# CharlieplexNameTag.net
KiCad netlist of a schematic drawn in EAGLE
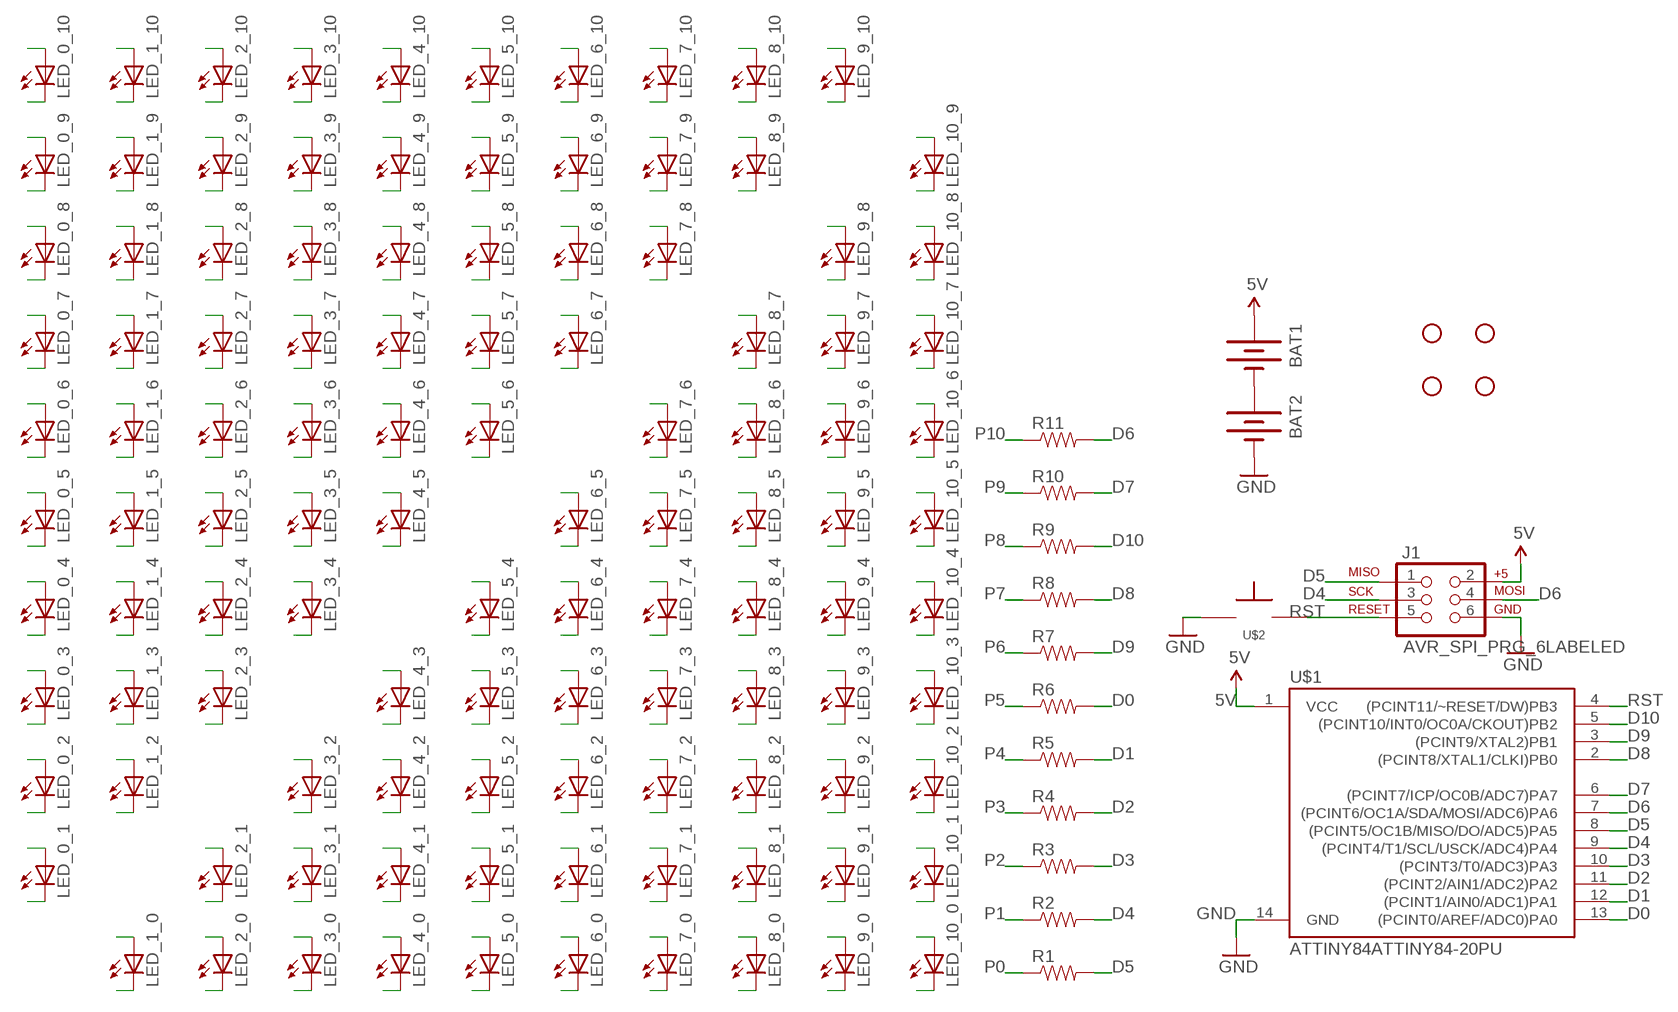
[diagram p0: schematic, sheet 1]

(export (version "E")
  (design (tool "Eeschema 10.0.6"))
  (components
    (comp (ref "BAT1")
      (value "BATTERYAAA")
      (footprint "eagle-import:BATTERY-AAA")
      (libsource (lib "eagle-import") (part "BATTERYAAA"))
    )
    (comp (ref "BAT2")
      (value "BATTERYAAA")
      (footprint "eagle-import:BATTERY-AAA")
      (libsource (lib "eagle-import") (part "BATTERYAAA"))
    )
    (comp (ref "J1")
      (value "AVR_SPI_PRG_6LABELED")
      (footprint "eagle-import:2X3-NS")
      (libsource (lib "eagle-import") (part "AVR_SPI_PRG_6LABELED"))
    )
    (comp (ref "LED_0_1")
      (value "LED3MM")
      (footprint "eagle-import:LED3MM")
      (libsource (lib "eagle-import") (part "LED3MM"))
    )
    (comp (ref "LED_0_2")
      (value "LED3MM")
      (footprint "eagle-import:LED3MM")
      (libsource (lib "eagle-import") (part "LED3MM"))
    )
    (comp (ref "LED_0_3")
      (value "LED3MM")
      (footprint "eagle-import:LED3MM")
      (libsource (lib "eagle-import") (part "LED3MM"))
    )
    (comp (ref "LED_0_4")
      (value "LED3MM")
      (footprint "eagle-import:LED3MM")
      (libsource (lib "eagle-import") (part "LED3MM"))
    )
    (comp (ref "LED_0_5")
      (value "LED3MM")
      (footprint "eagle-import:LED3MM")
      (libsource (lib "eagle-import") (part "LED3MM"))
    )
    (comp (ref "LED_0_6")
      (value "LED3MM")
      (footprint "eagle-import:LED3MM")
      (libsource (lib "eagle-import") (part "LED3MM"))
    )
    (comp (ref "LED_0_7")
      (value "LED3MM")
      (footprint "eagle-import:LED3MM")
      (libsource (lib "eagle-import") (part "LED3MM"))
    )
    (comp (ref "LED_0_8")
      (value "LED3MM")
      (footprint "eagle-import:LED3MM")
      (libsource (lib "eagle-import") (part "LED3MM"))
    )
    (comp (ref "LED_0_9")
      (value "LED3MM")
      (footprint "eagle-import:LED3MM")
      (libsource (lib "eagle-import") (part "LED3MM"))
    )
    (comp (ref "LED_0_10")
      (value "LED3MM")
      (footprint "eagle-import:LED3MM")
      (libsource (lib "eagle-import") (part "LED3MM"))
    )
    (comp (ref "LED_1_0")
      (value "LED3MM")
      (footprint "eagle-import:LED3MM")
      (libsource (lib "eagle-import") (part "LED3MM"))
    )
    (comp (ref "LED_1_2")
      (value "LED3MM")
      (footprint "eagle-import:LED3MM")
      (libsource (lib "eagle-import") (part "LED3MM"))
    )
    (comp (ref "LED_1_3")
      (value "LED3MM")
      (footprint "eagle-import:LED3MM")
      (libsource (lib "eagle-import") (part "LED3MM"))
    )
    (comp (ref "LED_1_4")
      (value "LED3MM")
      (footprint "eagle-import:LED3MM")
      (libsource (lib "eagle-import") (part "LED3MM"))
    )
    (comp (ref "LED_1_5")
      (value "LED3MM")
      (footprint "eagle-import:LED3MM")
      (libsource (lib "eagle-import") (part "LED3MM"))
    )
    (comp (ref "LED_1_6")
      (value "LED3MM")
      (footprint "eagle-import:LED3MM")
      (libsource (lib "eagle-import") (part "LED3MM"))
    )
    (comp (ref "LED_1_7")
      (value "LED3MM")
      (footprint "eagle-import:LED3MM")
      (libsource (lib "eagle-import") (part "LED3MM"))
    )
    (comp (ref "LED_1_8")
      (value "LED3MM")
      (footprint "eagle-import:LED3MM")
      (libsource (lib "eagle-import") (part "LED3MM"))
    )
    (comp (ref "LED_1_9")
      (value "LED3MM")
      (footprint "eagle-import:LED3MM")
      (libsource (lib "eagle-import") (part "LED3MM"))
    )
    (comp (ref "LED_1_10")
      (value "LED3MM")
      (footprint "eagle-import:LED3MM")
      (libsource (lib "eagle-import") (part "LED3MM"))
    )
    (comp (ref "LED_2_0")
      (value "LED3MM")
      (footprint "eagle-import:LED3MM")
      (libsource (lib "eagle-import") (part "LED3MM"))
    )
    (comp (ref "LED_2_1")
      (value "LED3MM")
      (footprint "eagle-import:LED3MM")
      (libsource (lib "eagle-import") (part "LED3MM"))
    )
    (comp (ref "LED_2_3")
      (value "LED3MM")
      (footprint "eagle-import:LED3MM")
      (libsource (lib "eagle-import") (part "LED3MM"))
    )
    (comp (ref "LED_2_4")
      (value "LED3MM")
      (footprint "eagle-import:LED3MM")
      (libsource (lib "eagle-import") (part "LED3MM"))
    )
    (comp (ref "LED_2_5")
      (value "LED3MM")
      (footprint "eagle-import:LED3MM")
      (libsource (lib "eagle-import") (part "LED3MM"))
    )
    (comp (ref "LED_2_6")
      (value "LED3MM")
      (footprint "eagle-import:LED3MM")
      (libsource (lib "eagle-import") (part "LED3MM"))
    )
    (comp (ref "LED_2_7")
      (value "LED3MM")
      (footprint "eagle-import:LED3MM")
      (libsource (lib "eagle-import") (part "LED3MM"))
    )
    (comp (ref "LED_2_8")
      (value "LED3MM")
      (footprint "eagle-import:LED3MM")
      (libsource (lib "eagle-import") (part "LED3MM"))
    )
    (comp (ref "LED_2_9")
      (value "LED3MM")
      (footprint "eagle-import:LED3MM")
      (libsource (lib "eagle-import") (part "LED3MM"))
    )
    (comp (ref "LED_2_10")
      (value "LED3MM")
      (footprint "eagle-import:LED3MM")
      (libsource (lib "eagle-import") (part "LED3MM"))
    )
    (comp (ref "LED_3_0")
      (value "LED3MM")
      (footprint "eagle-import:LED3MM")
      (libsource (lib "eagle-import") (part "LED3MM"))
    )
    (comp (ref "LED_3_1")
      (value "LED3MM")
      (footprint "eagle-import:LED3MM")
      (libsource (lib "eagle-import") (part "LED3MM"))
    )
    (comp (ref "LED_3_2")
      (value "LED3MM")
      (footprint "eagle-import:LED3MM")
      (libsource (lib "eagle-import") (part "LED3MM"))
    )
    (comp (ref "LED_3_4")
      (value "LED3MM")
      (footprint "eagle-import:LED3MM")
      (libsource (lib "eagle-import") (part "LED3MM"))
    )
    (comp (ref "LED_3_5")
      (value "LED3MM")
      (footprint "eagle-import:LED3MM")
      (libsource (lib "eagle-import") (part "LED3MM"))
    )
    (comp (ref "LED_3_6")
      (value "LED3MM")
      (footprint "eagle-import:LED3MM")
      (libsource (lib "eagle-import") (part "LED3MM"))
    )
    (comp (ref "LED_3_7")
      (value "LED3MM")
      (footprint "eagle-import:LED3MM")
      (libsource (lib "eagle-import") (part "LED3MM"))
    )
    (comp (ref "LED_3_8")
      (value "LED3MM")
      (footprint "eagle-import:LED3MM")
      (libsource (lib "eagle-import") (part "LED3MM"))
    )
    (comp (ref "LED_3_9")
      (value "LED3MM")
      (footprint "eagle-import:LED3MM")
      (libsource (lib "eagle-import") (part "LED3MM"))
    )
    (comp (ref "LED_3_10")
      (value "LED3MM")
      (footprint "eagle-import:LED3MM")
      (libsource (lib "eagle-import") (part "LED3MM"))
    )
    (comp (ref "LED_4_0")
      (value "LED3MM")
      (footprint "eagle-import:LED3MM")
      (libsource (lib "eagle-import") (part "LED3MM"))
    )
    (comp (ref "LED_4_1")
      (value "LED3MM")
      (footprint "eagle-import:LED3MM")
      (libsource (lib "eagle-import") (part "LED3MM"))
    )
    (comp (ref "LED_4_2")
      (value "LED3MM")
      (footprint "eagle-import:LED3MM")
      (libsource (lib "eagle-import") (part "LED3MM"))
    )
    (comp (ref "LED_4_3")
      (value "LED3MM")
      (footprint "eagle-import:LED3MM")
      (libsource (lib "eagle-import") (part "LED3MM"))
    )
    (comp (ref "LED_4_5")
      (value "LED3MM")
      (footprint "eagle-import:LED3MM")
      (libsource (lib "eagle-import") (part "LED3MM"))
    )
    (comp (ref "LED_4_6")
      (value "LED3MM")
      (footprint "eagle-import:LED3MM")
      (libsource (lib "eagle-import") (part "LED3MM"))
    )
    (comp (ref "LED_4_7")
      (value "LED3MM")
      (footprint "eagle-import:LED3MM")
      (libsource (lib "eagle-import") (part "LED3MM"))
    )
    (comp (ref "LED_4_8")
      (value "LED3MM")
      (footprint "eagle-import:LED3MM")
      (libsource (lib "eagle-import") (part "LED3MM"))
    )
    (comp (ref "LED_4_9")
      (value "LED3MM")
      (footprint "eagle-import:LED3MM")
      (libsource (lib "eagle-import") (part "LED3MM"))
    )
    (comp (ref "LED_4_10")
      (value "LED3MM")
      (footprint "eagle-import:LED3MM")
      (libsource (lib "eagle-import") (part "LED3MM"))
    )
    (comp (ref "LED_5_0")
      (value "LED3MM")
      (footprint "eagle-import:LED3MM")
      (libsource (lib "eagle-import") (part "LED3MM"))
    )
    (comp (ref "LED_5_1")
      (value "LED3MM")
      (footprint "eagle-import:LED3MM")
      (libsource (lib "eagle-import") (part "LED3MM"))
    )
    (comp (ref "LED_5_2")
      (value "LED3MM")
      (footprint "eagle-import:LED3MM")
      (libsource (lib "eagle-import") (part "LED3MM"))
    )
    (comp (ref "LED_5_3")
      (value "LED3MM")
      (footprint "eagle-import:LED3MM")
      (libsource (lib "eagle-import") (part "LED3MM"))
    )
    (comp (ref "LED_5_4")
      (value "LED3MM")
      (footprint "eagle-import:LED3MM")
      (libsource (lib "eagle-import") (part "LED3MM"))
    )
    (comp (ref "LED_5_6")
      (value "LED3MM")
      (footprint "eagle-import:LED3MM")
      (libsource (lib "eagle-import") (part "LED3MM"))
    )
    (comp (ref "LED_5_7")
      (value "LED3MM")
      (footprint "eagle-import:LED3MM")
      (libsource (lib "eagle-import") (part "LED3MM"))
    )
    (comp (ref "LED_5_8")
      (value "LED3MM")
      (footprint "eagle-import:LED3MM")
      (libsource (lib "eagle-import") (part "LED3MM"))
    )
    (comp (ref "LED_5_9")
      (value "LED3MM")
      (footprint "eagle-import:LED3MM")
      (libsource (lib "eagle-import") (part "LED3MM"))
    )
    (comp (ref "LED_5_10")
      (value "LED3MM")
      (footprint "eagle-import:LED3MM")
      (libsource (lib "eagle-import") (part "LED3MM"))
    )
    (comp (ref "LED_6_0")
      (value "LED3MM")
      (footprint "eagle-import:LED3MM")
      (libsource (lib "eagle-import") (part "LED3MM"))
    )
    (comp (ref "LED_6_1")
      (value "LED3MM")
      (footprint "eagle-import:LED3MM")
      (libsource (lib "eagle-import") (part "LED3MM"))
    )
    (comp (ref "LED_6_2")
      (value "LED3MM")
      (footprint "eagle-import:LED3MM")
      (libsource (lib "eagle-import") (part "LED3MM"))
    )
    (comp (ref "LED_6_3")
      (value "LED3MM")
      (footprint "eagle-import:LED3MM")
      (libsource (lib "eagle-import") (part "LED3MM"))
    )
    (comp (ref "LED_6_4")
      (value "LED3MM")
      (footprint "eagle-import:LED3MM")
      (libsource (lib "eagle-import") (part "LED3MM"))
    )
    (comp (ref "LED_6_5")
      (value "LED3MM")
      (footprint "eagle-import:LED3MM")
      (libsource (lib "eagle-import") (part "LED3MM"))
    )
    (comp (ref "LED_6_7")
      (value "LED3MM")
      (footprint "eagle-import:LED3MM")
      (libsource (lib "eagle-import") (part "LED3MM"))
    )
    (comp (ref "LED_6_8")
      (value "LED3MM")
      (footprint "eagle-import:LED3MM")
      (libsource (lib "eagle-import") (part "LED3MM"))
    )
    (comp (ref "LED_6_9")
      (value "LED3MM")
      (footprint "eagle-import:LED3MM")
      (libsource (lib "eagle-import") (part "LED3MM"))
    )
    (comp (ref "LED_6_10")
      (value "LED3MM")
      (footprint "eagle-import:LED3MM")
      (libsource (lib "eagle-import") (part "LED3MM"))
    )
    (comp (ref "LED_7_0")
      (value "LED3MM")
      (footprint "eagle-import:LED3MM")
      (libsource (lib "eagle-import") (part "LED3MM"))
    )
    (comp (ref "LED_7_1")
      (value "LED3MM")
      (footprint "eagle-import:LED3MM")
      (libsource (lib "eagle-import") (part "LED3MM"))
    )
    (comp (ref "LED_7_2")
      (value "LED3MM")
      (footprint "eagle-import:LED3MM")
      (libsource (lib "eagle-import") (part "LED3MM"))
    )
    (comp (ref "LED_7_3")
      (value "LED3MM")
      (footprint "eagle-import:LED3MM")
      (libsource (lib "eagle-import") (part "LED3MM"))
    )
    (comp (ref "LED_7_4")
      (value "LED3MM")
      (footprint "eagle-import:LED3MM")
      (libsource (lib "eagle-import") (part "LED3MM"))
    )
    (comp (ref "LED_7_5")
      (value "LED3MM")
      (footprint "eagle-import:LED3MM")
      (libsource (lib "eagle-import") (part "LED3MM"))
    )
    (comp (ref "LED_7_6")
      (value "LED3MM")
      (footprint "eagle-import:LED3MM")
      (libsource (lib "eagle-import") (part "LED3MM"))
    )
    (comp (ref "LED_7_8")
      (value "LED3MM")
      (footprint "eagle-import:LED3MM")
      (libsource (lib "eagle-import") (part "LED3MM"))
    )
    (comp (ref "LED_7_9")
      (value "LED3MM")
      (footprint "eagle-import:LED3MM")
      (libsource (lib "eagle-import") (part "LED3MM"))
    )
    (comp (ref "LED_7_10")
      (value "LED3MM")
      (footprint "eagle-import:LED3MM")
      (libsource (lib "eagle-import") (part "LED3MM"))
    )
    (comp (ref "LED_8_0")
      (value "LED3MM")
      (footprint "eagle-import:LED3MM")
      (libsource (lib "eagle-import") (part "LED3MM"))
    )
    (comp (ref "LED_8_1")
      (value "LED3MM")
      (footprint "eagle-import:LED3MM")
      (libsource (lib "eagle-import") (part "LED3MM"))
    )
    (comp (ref "LED_8_2")
      (value "LED3MM")
      (footprint "eagle-import:LED3MM")
      (libsource (lib "eagle-import") (part "LED3MM"))
    )
    (comp (ref "LED_8_3")
      (value "LED3MM")
      (footprint "eagle-import:LED3MM")
      (libsource (lib "eagle-import") (part "LED3MM"))
    )
    (comp (ref "LED_8_4")
      (value "LED3MM")
      (footprint "eagle-import:LED3MM")
      (libsource (lib "eagle-import") (part "LED3MM"))
    )
    (comp (ref "LED_8_5")
      (value "LED3MM")
      (footprint "eagle-import:LED3MM")
      (libsource (lib "eagle-import") (part "LED3MM"))
    )
    (comp (ref "LED_8_6")
      (value "LED3MM")
      (footprint "eagle-import:LED3MM")
      (libsource (lib "eagle-import") (part "LED3MM"))
    )
    (comp (ref "LED_8_7")
      (value "LED3MM")
      (footprint "eagle-import:LED3MM")
      (libsource (lib "eagle-import") (part "LED3MM"))
    )
    (comp (ref "LED_8_9")
      (value "LED3MM")
      (footprint "eagle-import:LED3MM")
      (libsource (lib "eagle-import") (part "LED3MM"))
    )
    (comp (ref "LED_8_10")
      (value "LED3MM")
      (footprint "eagle-import:LED3MM")
      (libsource (lib "eagle-import") (part "LED3MM"))
    )
    (comp (ref "LED_9_0")
      (value "LED3MM")
      (footprint "eagle-import:LED3MM")
      (libsource (lib "eagle-import") (part "LED3MM"))
    )
    (comp (ref "LED_9_1")
      (value "LED3MM")
      (footprint "eagle-import:LED3MM")
      (libsource (lib "eagle-import") (part "LED3MM"))
    )
    (comp (ref "LED_9_2")
      (value "LED3MM")
      (footprint "eagle-import:LED3MM")
      (libsource (lib "eagle-import") (part "LED3MM"))
    )
    (comp (ref "LED_9_3")
      (value "LED3MM")
      (footprint "eagle-import:LED3MM")
      (libsource (lib "eagle-import") (part "LED3MM"))
    )
    (comp (ref "LED_9_4")
      (value "LED3MM")
      (footprint "eagle-import:LED3MM")
      (libsource (lib "eagle-import") (part "LED3MM"))
    )
    (comp (ref "LED_9_5")
      (value "LED3MM")
      (footprint "eagle-import:LED3MM")
      (libsource (lib "eagle-import") (part "LED3MM"))
    )
    (comp (ref "LED_9_6")
      (value "LED3MM")
      (footprint "eagle-import:LED3MM")
      (libsource (lib "eagle-import") (part "LED3MM"))
    )
    (comp (ref "LED_9_7")
      (value "LED3MM")
      (footprint "eagle-import:LED3MM")
      (libsource (lib "eagle-import") (part "LED3MM"))
    )
    (comp (ref "LED_9_8")
      (value "LED3MM")
      (footprint "eagle-import:LED3MM")
      (libsource (lib "eagle-import") (part "LED3MM"))
    )
    (comp (ref "LED_9_10")
      (value "LED3MM")
      (footprint "eagle-import:LED3MM")
      (libsource (lib "eagle-import") (part "LED3MM"))
    )
    (comp (ref "LED_10_0")
      (value "LED3MM")
      (footprint "eagle-import:LED3MM")
      (libsource (lib "eagle-import") (part "LED3MM"))
    )
    (comp (ref "LED_10_1")
      (value "LED3MM")
      (footprint "eagle-import:LED3MM")
      (libsource (lib "eagle-import") (part "LED3MM"))
    )
    (comp (ref "LED_10_2")
      (value "LED3MM")
      (footprint "eagle-import:LED3MM")
      (libsource (lib "eagle-import") (part "LED3MM"))
    )
    (comp (ref "LED_10_3")
      (value "LED3MM")
      (footprint "eagle-import:LED3MM")
      (libsource (lib "eagle-import") (part "LED3MM"))
    )
    (comp (ref "LED_10_4")
      (value "LED3MM")
      (footprint "eagle-import:LED3MM")
      (libsource (lib "eagle-import") (part "LED3MM"))
    )
    (comp (ref "LED_10_5")
      (value "LED3MM")
      (footprint "eagle-import:LED3MM")
      (libsource (lib "eagle-import") (part "LED3MM"))
    )
    (comp (ref "LED_10_6")
      (value "LED3MM")
      (footprint "eagle-import:LED3MM")
      (libsource (lib "eagle-import") (part "LED3MM"))
    )
    (comp (ref "LED_10_7")
      (value "LED3MM")
      (footprint "eagle-import:LED3MM")
      (libsource (lib "eagle-import") (part "LED3MM"))
    )
    (comp (ref "LED_10_8")
      (value "LED3MM")
      (footprint "eagle-import:LED3MM")
      (libsource (lib "eagle-import") (part "LED3MM"))
    )
    (comp (ref "LED_10_9")
      (value "LED3MM")
      (footprint "eagle-import:LED3MM")
      (libsource (lib "eagle-import") (part "LED3MM"))
    )
    (comp (ref "R1")
      (value "RESISTORAXIAL-0.3")
      (footprint "eagle-import:AXIAL-0.3")
      (libsource (lib "eagle-import") (part "RESISTORAXIAL-0.3"))
    )
    (comp (ref "R2")
      (value "RESISTORAXIAL-0.3")
      (footprint "eagle-import:AXIAL-0.3")
      (libsource (lib "eagle-import") (part "RESISTORAXIAL-0.3"))
    )
    (comp (ref "R3")
      (value "RESISTORAXIAL-0.3")
      (footprint "eagle-import:AXIAL-0.3")
      (libsource (lib "eagle-import") (part "RESISTORAXIAL-0.3"))
    )
    (comp (ref "R4")
      (value "RESISTORAXIAL-0.3")
      (footprint "eagle-import:AXIAL-0.3")
      (libsource (lib "eagle-import") (part "RESISTORAXIAL-0.3"))
    )
    (comp (ref "R5")
      (value "RESISTORAXIAL-0.3")
      (footprint "eagle-import:AXIAL-0.3")
      (libsource (lib "eagle-import") (part "RESISTORAXIAL-0.3"))
    )
    (comp (ref "R6")
      (value "RESISTORAXIAL-0.3")
      (footprint "eagle-import:AXIAL-0.3")
      (libsource (lib "eagle-import") (part "RESISTORAXIAL-0.3"))
    )
    (comp (ref "R7")
      (value "RESISTORAXIAL-0.3")
      (footprint "eagle-import:AXIAL-0.3")
      (libsource (lib "eagle-import") (part "RESISTORAXIAL-0.3"))
    )
    (comp (ref "R8")
      (value "RESISTORAXIAL-0.3")
      (footprint "eagle-import:AXIAL-0.3")
      (libsource (lib "eagle-import") (part "RESISTORAXIAL-0.3"))
    )
    (comp (ref "R9")
      (value "RESISTORAXIAL-0.3")
      (footprint "eagle-import:AXIAL-0.3")
      (libsource (lib "eagle-import") (part "RESISTORAXIAL-0.3"))
    )
    (comp (ref "R10")
      (value "RESISTORAXIAL-0.3")
      (footprint "eagle-import:AXIAL-0.3")
      (libsource (lib "eagle-import") (part "RESISTORAXIAL-0.3"))
    )
    (comp (ref "R11")
      (value "RESISTORAXIAL-0.3")
      (footprint "eagle-import:AXIAL-0.3")
      (libsource (lib "eagle-import") (part "RESISTORAXIAL-0.3"))
    )
    (comp (ref "STANDOFF1")
      (value "STAND-OFF")
      (footprint "eagle-import:STAND-OFF")
      (libsource (lib "eagle-import") (part "STAND-OFF"))
    )
    (comp (ref "STANDOFF2")
      (value "STAND-OFF")
      (footprint "eagle-import:STAND-OFF")
      (libsource (lib "eagle-import") (part "STAND-OFF"))
    )
    (comp (ref "STANDOFF3")
      (value "STAND-OFF")
      (footprint "eagle-import:STAND-OFF")
      (libsource (lib "eagle-import") (part "STAND-OFF"))
    )
    (comp (ref "STANDOFF4")
      (value "STAND-OFF")
      (footprint "eagle-import:STAND-OFF")
      (libsource (lib "eagle-import") (part "STAND-OFF"))
    )
    (comp (ref "U$1")
      (value "ATTINY84ATTINY84-20PU")
      (footprint "eagle-import:DIL14")
      (libsource (lib "eagle-import") (part "ATTINY84ATTINY84-20PU"))
    )
    (comp (ref "U$2")
      (value "TAC_SPST_NO")
      (footprint "eagle-import:TAC_SPST_NO")
      (libsource (lib "eagle-import") (part "TAC_SPST_NO"))
    )
  )
  (nets
    (net (code "1") (name "/D0") (class "Default")
      (node (ref "R6") (pin "P$2") (pinfunction "2_P$2") (pintype "passive"))
      (node (ref "U$1") (pin "13") (pinfunction "(PCINT0/AREF/ADC0)PA0_13") (pintype "bidirectional"))
    )
    (net (code "2") (name "/D1") (class "Default")
      (node (ref "R5") (pin "P$2") (pinfunction "2_P$2") (pintype "passive"))
      (node (ref "U$1") (pin "12") (pinfunction "(PCINT1/AIN0/ADC1)PA1_12") (pintype "bidirectional"))
    )
    (net (code "3") (name "/D2") (class "Default")
      (node (ref "R4") (pin "P$2") (pinfunction "2_P$2") (pintype "passive"))
      (node (ref "U$1") (pin "11") (pinfunction "(PCINT2/AIN1/ADC2)PA2_11") (pintype "bidirectional"))
    )
    (net (code "4") (name "/D3") (class "Default")
      (node (ref "R3") (pin "P$2") (pinfunction "2_P$2") (pintype "passive"))
      (node (ref "U$1") (pin "10") (pinfunction "(PCINT3/T0/ADC3)PA3_10") (pintype "bidirectional"))
    )
    (net (code "5") (name "/D4") (class "Default")
      (node (ref "J1") (pin "3") (pinfunction "3_3") (pintype "passive"))
      (node (ref "R2") (pin "P$2") (pinfunction "2_P$2") (pintype "passive"))
      (node (ref "U$1") (pin "9") (pinfunction "(PCINT4/T1/SCL/USCK/ADC4)PA4_9") (pintype "bidirectional"))
    )
    (net (code "6") (name "/D5") (class "Default")
      (node (ref "J1") (pin "1") (pinfunction "1_1") (pintype "passive"))
      (node (ref "R1") (pin "P$2") (pinfunction "2_P$2") (pintype "passive"))
      (node (ref "U$1") (pin "8") (pinfunction "(PCINT5/OC1B/MISO/DO/ADC5)PA5_8") (pintype "bidirectional"))
    )
    (net (code "7") (name "/D6") (class "Default")
      (node (ref "J1") (pin "4") (pinfunction "4_4") (pintype "passive"))
      (node (ref "R11") (pin "P$2") (pinfunction "2_P$2") (pintype "passive"))
      (node (ref "U$1") (pin "7") (pinfunction "(PCINT6/OC1A/SDA/MOSI/ADC6)PA6_7") (pintype "bidirectional"))
    )
    (net (code "8") (name "/D7") (class "Default")
      (node (ref "R10") (pin "P$2") (pinfunction "2_P$2") (pintype "passive"))
      (node (ref "U$1") (pin "6") (pinfunction "(PCINT7/ICP/OC0B/ADC7)PA7_6") (pintype "bidirectional"))
    )
    (net (code "9") (name "/D8") (class "Default")
      (node (ref "R8") (pin "P$2") (pinfunction "2_P$2") (pintype "passive"))
      (node (ref "U$1") (pin "2") (pinfunction "(PCINT8/XTAL1/CLKI)PB0_2") (pintype "bidirectional"))
    )
    (net (code "10") (name "/D9") (class "Default")
      (node (ref "R7") (pin "P$2") (pinfunction "2_P$2") (pintype "passive"))
      (node (ref "U$1") (pin "3") (pinfunction "(PCINT9/XTAL2)PB1_3") (pintype "bidirectional"))
    )
    (net (code "11") (name "/D10") (class "Default")
      (node (ref "R9") (pin "P$2") (pinfunction "2_P$2") (pintype "passive"))
      (node (ref "U$1") (pin "5") (pinfunction "(PCINT10/INT0/OC0A/CKOUT)PB2_5") (pintype "bidirectional"))
    )
    (net (code "12") (name "/P0") (class "Default")
      (node (ref "LED_0_1") (pin "K") (pinfunction "C_K") (pintype "passive"))
      (node (ref "LED_0_10") (pin "K") (pinfunction "C_K") (pintype "passive"))
      (node (ref "LED_0_2") (pin "K") (pinfunction "C_K") (pintype "passive"))
      (node (ref "LED_0_3") (pin "K") (pinfunction "C_K") (pintype "passive"))
      (node (ref "LED_0_4") (pin "K") (pinfunction "C_K") (pintype "passive"))
      (node (ref "LED_0_5") (pin "K") (pinfunction "C_K") (pintype "passive"))
      (node (ref "LED_0_6") (pin "K") (pinfunction "C_K") (pintype "passive"))
      (node (ref "LED_0_7") (pin "K") (pinfunction "C_K") (pintype "passive"))
      (node (ref "LED_0_8") (pin "K") (pinfunction "C_K") (pintype "passive"))
      (node (ref "LED_0_9") (pin "K") (pinfunction "C_K") (pintype "passive"))
      (node (ref "LED_10_0") (pin "A") (pinfunction "A_A") (pintype "passive"))
      (node (ref "LED_1_0") (pin "A") (pinfunction "A_A") (pintype "passive"))
      (node (ref "LED_2_0") (pin "A") (pinfunction "A_A") (pintype "passive"))
      (node (ref "LED_3_0") (pin "A") (pinfunction "A_A") (pintype "passive"))
      (node (ref "LED_4_0") (pin "A") (pinfunction "A_A") (pintype "passive"))
      (node (ref "LED_5_0") (pin "A") (pinfunction "A_A") (pintype "passive"))
      (node (ref "LED_6_0") (pin "A") (pinfunction "A_A") (pintype "passive"))
      (node (ref "LED_7_0") (pin "A") (pinfunction "A_A") (pintype "passive"))
      (node (ref "LED_8_0") (pin "A") (pinfunction "A_A") (pintype "passive"))
      (node (ref "LED_9_0") (pin "A") (pinfunction "A_A") (pintype "passive"))
      (node (ref "R1") (pin "P$1") (pinfunction "1_P$1") (pintype "passive"))
    )
    (net (code "13") (name "/P1") (class "Default")
      (node (ref "LED_0_1") (pin "A") (pinfunction "A_A") (pintype "passive"))
      (node (ref "LED_10_1") (pin "A") (pinfunction "A_A") (pintype "passive"))
      (node (ref "LED_1_0") (pin "K") (pinfunction "C_K") (pintype "passive"))
      (node (ref "LED_1_10") (pin "K") (pinfunction "C_K") (pintype "passive"))
      (node (ref "LED_1_2") (pin "K") (pinfunction "C_K") (pintype "passive"))
      (node (ref "LED_1_3") (pin "K") (pinfunction "C_K") (pintype "passive"))
      (node (ref "LED_1_4") (pin "K") (pinfunction "C_K") (pintype "passive"))
      (node (ref "LED_1_5") (pin "K") (pinfunction "C_K") (pintype "passive"))
      (node (ref "LED_1_6") (pin "K") (pinfunction "C_K") (pintype "passive"))
      (node (ref "LED_1_7") (pin "K") (pinfunction "C_K") (pintype "passive"))
      (node (ref "LED_1_8") (pin "K") (pinfunction "C_K") (pintype "passive"))
      (node (ref "LED_1_9") (pin "K") (pinfunction "C_K") (pintype "passive"))
      (node (ref "LED_2_1") (pin "A") (pinfunction "A_A") (pintype "passive"))
      (node (ref "LED_3_1") (pin "A") (pinfunction "A_A") (pintype "passive"))
      (node (ref "LED_4_1") (pin "A") (pinfunction "A_A") (pintype "passive"))
      (node (ref "LED_5_1") (pin "A") (pinfunction "A_A") (pintype "passive"))
      (node (ref "LED_6_1") (pin "A") (pinfunction "A_A") (pintype "passive"))
      (node (ref "LED_7_1") (pin "A") (pinfunction "A_A") (pintype "passive"))
      (node (ref "LED_8_1") (pin "A") (pinfunction "A_A") (pintype "passive"))
      (node (ref "LED_9_1") (pin "A") (pinfunction "A_A") (pintype "passive"))
      (node (ref "R2") (pin "P$1") (pinfunction "1_P$1") (pintype "passive"))
    )
    (net (code "14") (name "/P2") (class "Default")
      (node (ref "LED_0_2") (pin "A") (pinfunction "A_A") (pintype "passive"))
      (node (ref "LED_10_2") (pin "A") (pinfunction "A_A") (pintype "passive"))
      (node (ref "LED_1_2") (pin "A") (pinfunction "A_A") (pintype "passive"))
      (node (ref "LED_2_0") (pin "K") (pinfunction "C_K") (pintype "passive"))
      (node (ref "LED_2_1") (pin "K") (pinfunction "C_K") (pintype "passive"))
      (node (ref "LED_2_10") (pin "K") (pinfunction "C_K") (pintype "passive"))
      (node (ref "LED_2_3") (pin "K") (pinfunction "C_K") (pintype "passive"))
      (node (ref "LED_2_4") (pin "K") (pinfunction "C_K") (pintype "passive"))
      (node (ref "LED_2_5") (pin "K") (pinfunction "C_K") (pintype "passive"))
      (node (ref "LED_2_6") (pin "K") (pinfunction "C_K") (pintype "passive"))
      (node (ref "LED_2_7") (pin "K") (pinfunction "C_K") (pintype "passive"))
      (node (ref "LED_2_8") (pin "K") (pinfunction "C_K") (pintype "passive"))
      (node (ref "LED_2_9") (pin "K") (pinfunction "C_K") (pintype "passive"))
      (node (ref "LED_3_2") (pin "A") (pinfunction "A_A") (pintype "passive"))
      (node (ref "LED_4_2") (pin "A") (pinfunction "A_A") (pintype "passive"))
      (node (ref "LED_5_2") (pin "A") (pinfunction "A_A") (pintype "passive"))
      (node (ref "LED_6_2") (pin "A") (pinfunction "A_A") (pintype "passive"))
      (node (ref "LED_7_2") (pin "A") (pinfunction "A_A") (pintype "passive"))
      (node (ref "LED_8_2") (pin "A") (pinfunction "A_A") (pintype "passive"))
      (node (ref "LED_9_2") (pin "A") (pinfunction "A_A") (pintype "passive"))
      (node (ref "R3") (pin "P$1") (pinfunction "1_P$1") (pintype "passive"))
    )
    (net (code "15") (name "/P3") (class "Default")
      (node (ref "LED_0_3") (pin "A") (pinfunction "A_A") (pintype "passive"))
      (node (ref "LED_10_3") (pin "A") (pinfunction "A_A") (pintype "passive"))
      (node (ref "LED_1_3") (pin "A") (pinfunction "A_A") (pintype "passive"))
      (node (ref "LED_2_3") (pin "A") (pinfunction "A_A") (pintype "passive"))
      (node (ref "LED_3_0") (pin "K") (pinfunction "C_K") (pintype "passive"))
      (node (ref "LED_3_1") (pin "K") (pinfunction "C_K") (pintype "passive"))
      (node (ref "LED_3_10") (pin "K") (pinfunction "C_K") (pintype "passive"))
      (node (ref "LED_3_2") (pin "K") (pinfunction "C_K") (pintype "passive"))
      (node (ref "LED_3_4") (pin "K") (pinfunction "C_K") (pintype "passive"))
      (node (ref "LED_3_5") (pin "K") (pinfunction "C_K") (pintype "passive"))
      (node (ref "LED_3_6") (pin "K") (pinfunction "C_K") (pintype "passive"))
      (node (ref "LED_3_7") (pin "K") (pinfunction "C_K") (pintype "passive"))
      (node (ref "LED_3_8") (pin "K") (pinfunction "C_K") (pintype "passive"))
      (node (ref "LED_3_9") (pin "K") (pinfunction "C_K") (pintype "passive"))
      (node (ref "LED_4_3") (pin "A") (pinfunction "A_A") (pintype "passive"))
      (node (ref "LED_5_3") (pin "A") (pinfunction "A_A") (pintype "passive"))
      (node (ref "LED_6_3") (pin "A") (pinfunction "A_A") (pintype "passive"))
      (node (ref "LED_7_3") (pin "A") (pinfunction "A_A") (pintype "passive"))
      (node (ref "LED_8_3") (pin "A") (pinfunction "A_A") (pintype "passive"))
      (node (ref "LED_9_3") (pin "A") (pinfunction "A_A") (pintype "passive"))
      (node (ref "R4") (pin "P$1") (pinfunction "1_P$1") (pintype "passive"))
    )
    (net (code "16") (name "/P4") (class "Default")
      (node (ref "LED_0_4") (pin "A") (pinfunction "A_A") (pintype "passive"))
      (node (ref "LED_10_4") (pin "A") (pinfunction "A_A") (pintype "passive"))
      (node (ref "LED_1_4") (pin "A") (pinfunction "A_A") (pintype "passive"))
      (node (ref "LED_2_4") (pin "A") (pinfunction "A_A") (pintype "passive"))
      (node (ref "LED_3_4") (pin "A") (pinfunction "A_A") (pintype "passive"))
      (node (ref "LED_4_0") (pin "K") (pinfunction "C_K") (pintype "passive"))
      (node (ref "LED_4_1") (pin "K") (pinfunction "C_K") (pintype "passive"))
      (node (ref "LED_4_10") (pin "K") (pinfunction "C_K") (pintype "passive"))
      (node (ref "LED_4_2") (pin "K") (pinfunction "C_K") (pintype "passive"))
      (node (ref "LED_4_3") (pin "K") (pinfunction "C_K") (pintype "passive"))
      (node (ref "LED_4_5") (pin "K") (pinfunction "C_K") (pintype "passive"))
      (node (ref "LED_4_6") (pin "K") (pinfunction "C_K") (pintype "passive"))
      (node (ref "LED_4_7") (pin "K") (pinfunction "C_K") (pintype "passive"))
      (node (ref "LED_4_8") (pin "K") (pinfunction "C_K") (pintype "passive"))
      (node (ref "LED_4_9") (pin "K") (pinfunction "C_K") (pintype "passive"))
      (node (ref "LED_5_4") (pin "A") (pinfunction "A_A") (pintype "passive"))
      (node (ref "LED_6_4") (pin "A") (pinfunction "A_A") (pintype "passive"))
      (node (ref "LED_7_4") (pin "A") (pinfunction "A_A") (pintype "passive"))
      (node (ref "LED_8_4") (pin "A") (pinfunction "A_A") (pintype "passive"))
      (node (ref "LED_9_4") (pin "A") (pinfunction "A_A") (pintype "passive"))
      (node (ref "R5") (pin "P$1") (pinfunction "1_P$1") (pintype "passive"))
    )
    (net (code "17") (name "/P5") (class "Default")
      (node (ref "LED_0_5") (pin "A") (pinfunction "A_A") (pintype "passive"))
      (node (ref "LED_10_5") (pin "A") (pinfunction "A_A") (pintype "passive"))
      (node (ref "LED_1_5") (pin "A") (pinfunction "A_A") (pintype "passive"))
      (node (ref "LED_2_5") (pin "A") (pinfunction "A_A") (pintype "passive"))
      (node (ref "LED_3_5") (pin "A") (pinfunction "A_A") (pintype "passive"))
      (node (ref "LED_4_5") (pin "A") (pinfunction "A_A") (pintype "passive"))
      (node (ref "LED_5_0") (pin "K") (pinfunction "C_K") (pintype "passive"))
      (node (ref "LED_5_1") (pin "K") (pinfunction "C_K") (pintype "passive"))
      (node (ref "LED_5_10") (pin "K") (pinfunction "C_K") (pintype "passive"))
      (node (ref "LED_5_2") (pin "K") (pinfunction "C_K") (pintype "passive"))
      (node (ref "LED_5_3") (pin "K") (pinfunction "C_K") (pintype "passive"))
      (node (ref "LED_5_4") (pin "K") (pinfunction "C_K") (pintype "passive"))
      (node (ref "LED_5_6") (pin "K") (pinfunction "C_K") (pintype "passive"))
      (node (ref "LED_5_7") (pin "K") (pinfunction "C_K") (pintype "passive"))
      (node (ref "LED_5_8") (pin "K") (pinfunction "C_K") (pintype "passive"))
      (node (ref "LED_5_9") (pin "K") (pinfunction "C_K") (pintype "passive"))
      (node (ref "LED_6_5") (pin "A") (pinfunction "A_A") (pintype "passive"))
      (node (ref "LED_7_5") (pin "A") (pinfunction "A_A") (pintype "passive"))
      (node (ref "LED_8_5") (pin "A") (pinfunction "A_A") (pintype "passive"))
      (node (ref "LED_9_5") (pin "A") (pinfunction "A_A") (pintype "passive"))
      (node (ref "R6") (pin "P$1") (pinfunction "1_P$1") (pintype "passive"))
    )
    (net (code "18") (name "/P6") (class "Default")
      (node (ref "LED_0_6") (pin "A") (pinfunction "A_A") (pintype "passive"))
      (node (ref "LED_10_6") (pin "A") (pinfunction "A_A") (pintype "passive"))
      (node (ref "LED_1_6") (pin "A") (pinfunction "A_A") (pintype "passive"))
      (node (ref "LED_2_6") (pin "A") (pinfunction "A_A") (pintype "passive"))
      (node (ref "LED_3_6") (pin "A") (pinfunction "A_A") (pintype "passive"))
      (node (ref "LED_4_6") (pin "A") (pinfunction "A_A") (pintype "passive"))
      (node (ref "LED_5_6") (pin "A") (pinfunction "A_A") (pintype "passive"))
      (node (ref "LED_6_0") (pin "K") (pinfunction "C_K") (pintype "passive"))
      (node (ref "LED_6_1") (pin "K") (pinfunction "C_K") (pintype "passive"))
      (node (ref "LED_6_10") (pin "K") (pinfunction "C_K") (pintype "passive"))
      (node (ref "LED_6_2") (pin "K") (pinfunction "C_K") (pintype "passive"))
      (node (ref "LED_6_3") (pin "K") (pinfunction "C_K") (pintype "passive"))
      (node (ref "LED_6_4") (pin "K") (pinfunction "C_K") (pintype "passive"))
      (node (ref "LED_6_5") (pin "K") (pinfunction "C_K") (pintype "passive"))
      (node (ref "LED_6_7") (pin "K") (pinfunction "C_K") (pintype "passive"))
      (node (ref "LED_6_8") (pin "K") (pinfunction "C_K") (pintype "passive"))
      (node (ref "LED_6_9") (pin "K") (pinfunction "C_K") (pintype "passive"))
      (node (ref "LED_7_6") (pin "A") (pinfunction "A_A") (pintype "passive"))
      (node (ref "LED_8_6") (pin "A") (pinfunction "A_A") (pintype "passive"))
      (node (ref "LED_9_6") (pin "A") (pinfunction "A_A") (pintype "passive"))
      (node (ref "R7") (pin "P$1") (pinfunction "1_P$1") (pintype "passive"))
    )
    (net (code "19") (name "/P7") (class "Default")
      (node (ref "LED_0_7") (pin "A") (pinfunction "A_A") (pintype "passive"))
      (node (ref "LED_10_7") (pin "A") (pinfunction "A_A") (pintype "passive"))
      (node (ref "LED_1_7") (pin "A") (pinfunction "A_A") (pintype "passive"))
      (node (ref "LED_2_7") (pin "A") (pinfunction "A_A") (pintype "passive"))
      (node (ref "LED_3_7") (pin "A") (pinfunction "A_A") (pintype "passive"))
      (node (ref "LED_4_7") (pin "A") (pinfunction "A_A") (pintype "passive"))
      (node (ref "LED_5_7") (pin "A") (pinfunction "A_A") (pintype "passive"))
      (node (ref "LED_6_7") (pin "A") (pinfunction "A_A") (pintype "passive"))
      (node (ref "LED_7_0") (pin "K") (pinfunction "C_K") (pintype "passive"))
      (node (ref "LED_7_1") (pin "K") (pinfunction "C_K") (pintype "passive"))
      (node (ref "LED_7_10") (pin "K") (pinfunction "C_K") (pintype "passive"))
      (node (ref "LED_7_2") (pin "K") (pinfunction "C_K") (pintype "passive"))
      (node (ref "LED_7_3") (pin "K") (pinfunction "C_K") (pintype "passive"))
      (node (ref "LED_7_4") (pin "K") (pinfunction "C_K") (pintype "passive"))
      (node (ref "LED_7_5") (pin "K") (pinfunction "C_K") (pintype "passive"))
      (node (ref "LED_7_6") (pin "K") (pinfunction "C_K") (pintype "passive"))
      (node (ref "LED_7_8") (pin "K") (pinfunction "C_K") (pintype "passive"))
      (node (ref "LED_7_9") (pin "K") (pinfunction "C_K") (pintype "passive"))
      (node (ref "LED_8_7") (pin "A") (pinfunction "A_A") (pintype "passive"))
      (node (ref "LED_9_7") (pin "A") (pinfunction "A_A") (pintype "passive"))
      (node (ref "R8") (pin "P$1") (pinfunction "1_P$1") (pintype "passive"))
    )
    (net (code "20") (name "/P8") (class "Default")
      (node (ref "LED_0_8") (pin "A") (pinfunction "A_A") (pintype "passive"))
      (node (ref "LED_10_8") (pin "A") (pinfunction "A_A") (pintype "passive"))
      (node (ref "LED_1_8") (pin "A") (pinfunction "A_A") (pintype "passive"))
      (node (ref "LED_2_8") (pin "A") (pinfunction "A_A") (pintype "passive"))
      (node (ref "LED_3_8") (pin "A") (pinfunction "A_A") (pintype "passive"))
      (node (ref "LED_4_8") (pin "A") (pinfunction "A_A") (pintype "passive"))
      (node (ref "LED_5_8") (pin "A") (pinfunction "A_A") (pintype "passive"))
      (node (ref "LED_6_8") (pin "A") (pinfunction "A_A") (pintype "passive"))
      (node (ref "LED_7_8") (pin "A") (pinfunction "A_A") (pintype "passive"))
      (node (ref "LED_8_0") (pin "K") (pinfunction "C_K") (pintype "passive"))
      (node (ref "LED_8_1") (pin "K") (pinfunction "C_K") (pintype "passive"))
      (node (ref "LED_8_10") (pin "K") (pinfunction "C_K") (pintype "passive"))
      (node (ref "LED_8_2") (pin "K") (pinfunction "C_K") (pintype "passive"))
      (node (ref "LED_8_3") (pin "K") (pinfunction "C_K") (pintype "passive"))
      (node (ref "LED_8_4") (pin "K") (pinfunction "C_K") (pintype "passive"))
      (node (ref "LED_8_5") (pin "K") (pinfunction "C_K") (pintype "passive"))
      (node (ref "LED_8_6") (pin "K") (pinfunction "C_K") (pintype "passive"))
      (node (ref "LED_8_7") (pin "K") (pinfunction "C_K") (pintype "passive"))
      (node (ref "LED_8_9") (pin "K") (pinfunction "C_K") (pintype "passive"))
      (node (ref "LED_9_8") (pin "A") (pinfunction "A_A") (pintype "passive"))
      (node (ref "R9") (pin "P$1") (pinfunction "1_P$1") (pintype "passive"))
    )
    (net (code "21") (name "/P9") (class "Default")
      (node (ref "LED_0_9") (pin "A") (pinfunction "A_A") (pintype "passive"))
      (node (ref "LED_10_9") (pin "A") (pinfunction "A_A") (pintype "passive"))
      (node (ref "LED_1_9") (pin "A") (pinfunction "A_A") (pintype "passive"))
      (node (ref "LED_2_9") (pin "A") (pinfunction "A_A") (pintype "passive"))
      (node (ref "LED_3_9") (pin "A") (pinfunction "A_A") (pintype "passive"))
      (node (ref "LED_4_9") (pin "A") (pinfunction "A_A") (pintype "passive"))
      (node (ref "LED_5_9") (pin "A") (pinfunction "A_A") (pintype "passive"))
      (node (ref "LED_6_9") (pin "A") (pinfunction "A_A") (pintype "passive"))
      (node (ref "LED_7_9") (pin "A") (pinfunction "A_A") (pintype "passive"))
      (node (ref "LED_8_9") (pin "A") (pinfunction "A_A") (pintype "passive"))
      (node (ref "LED_9_0") (pin "K") (pinfunction "C_K") (pintype "passive"))
      (node (ref "LED_9_1") (pin "K") (pinfunction "C_K") (pintype "passive"))
      (node (ref "LED_9_10") (pin "K") (pinfunction "C_K") (pintype "passive"))
      (node (ref "LED_9_2") (pin "K") (pinfunction "C_K") (pintype "passive"))
      (node (ref "LED_9_3") (pin "K") (pinfunction "C_K") (pintype "passive"))
      (node (ref "LED_9_4") (pin "K") (pinfunction "C_K") (pintype "passive"))
      (node (ref "LED_9_5") (pin "K") (pinfunction "C_K") (pintype "passive"))
      (node (ref "LED_9_6") (pin "K") (pinfunction "C_K") (pintype "passive"))
      (node (ref "LED_9_7") (pin "K") (pinfunction "C_K") (pintype "passive"))
      (node (ref "LED_9_8") (pin "K") (pinfunction "C_K") (pintype "passive"))
      (node (ref "R10") (pin "P$1") (pinfunction "1_P$1") (pintype "passive"))
    )
    (net (code "22") (name "/P10") (class "Default")
      (node (ref "LED_0_10") (pin "A") (pinfunction "A_A") (pintype "passive"))
      (node (ref "LED_10_0") (pin "K") (pinfunction "C_K") (pintype "passive"))
      (node (ref "LED_10_1") (pin "K") (pinfunction "C_K") (pintype "passive"))
      (node (ref "LED_10_2") (pin "K") (pinfunction "C_K") (pintype "passive"))
      (node (ref "LED_10_3") (pin "K") (pinfunction "C_K") (pintype "passive"))
      (node (ref "LED_10_4") (pin "K") (pinfunction "C_K") (pintype "passive"))
      (node (ref "LED_10_5") (pin "K") (pinfunction "C_K") (pintype "passive"))
      (node (ref "LED_10_6") (pin "K") (pinfunction "C_K") (pintype "passive"))
      (node (ref "LED_10_7") (pin "K") (pinfunction "C_K") (pintype "passive"))
      (node (ref "LED_10_8") (pin "K") (pinfunction "C_K") (pintype "passive"))
      (node (ref "LED_10_9") (pin "K") (pinfunction "C_K") (pintype "passive"))
      (node (ref "LED_1_10") (pin "A") (pinfunction "A_A") (pintype "passive"))
      (node (ref "LED_2_10") (pin "A") (pinfunction "A_A") (pintype "passive"))
      (node (ref "LED_3_10") (pin "A") (pinfunction "A_A") (pintype "passive"))
      (node (ref "LED_4_10") (pin "A") (pinfunction "A_A") (pintype "passive"))
      (node (ref "LED_5_10") (pin "A") (pinfunction "A_A") (pintype "passive"))
      (node (ref "LED_6_10") (pin "A") (pinfunction "A_A") (pintype "passive"))
      (node (ref "LED_7_10") (pin "A") (pinfunction "A_A") (pintype "passive"))
      (node (ref "LED_8_10") (pin "A") (pinfunction "A_A") (pintype "passive"))
      (node (ref "LED_9_10") (pin "A") (pinfunction "A_A") (pintype "passive"))
      (node (ref "R11") (pin "P$1") (pinfunction "1_P$1") (pintype "passive"))
    )
    (net (code "23") (name "/RST") (class "Default")
      (node (ref "J1") (pin "5") (pinfunction "5_5") (pintype "passive"))
      (node (ref "U$1") (pin "4") (pinfunction "(PCINT11/~{RESET/DW})PB3_4") (pintype "bidirectional"))
      (node (ref "U$2") (pin "P$2") (pinfunction "P$2_P$2") (pintype "bidirectional"))
    )
    (net (code "24") (name "5V") (class "Default")
      (node (ref "BAT1") (pin "PWR@1") (pinfunction "+_PWR@1") (pintype "power_in"))
      (node (ref "J1") (pin "2") (pinfunction "2_2") (pintype "passive"))
      (node (ref "U$1") (pin "1") (pinfunction "VCC_1") (pintype "bidirectional"))
    )
    (net (code "25") (name "GND") (class "Default")
      (node (ref "BAT2") (pin "GND@1") (pinfunction "-_GND@1") (pintype "power_in"))
      (node (ref "J1") (pin "6") (pinfunction "6_6") (pintype "passive"))
      (node (ref "U$1") (pin "14") (pinfunction "GND_14") (pintype "bidirectional"))
      (node (ref "U$2") (pin "P$1") (pinfunction "P$1_P$1") (pintype "bidirectional"))
    )
    (net (code "26") (name "Net-(BAT1--)") (class "Default")
      (node (ref "BAT1") (pin "GND@1") (pinfunction "-_GND@1") (pintype "power_in"))
      (node (ref "BAT2") (pin "PWR@1") (pinfunction "+_PWR@1") (pintype "power_in"))
    )
  )
)
